# TMotor_Rev0_5_1_Mark_2_MAR17.net
KiCad netlist of a schematic drawn in EAGLE
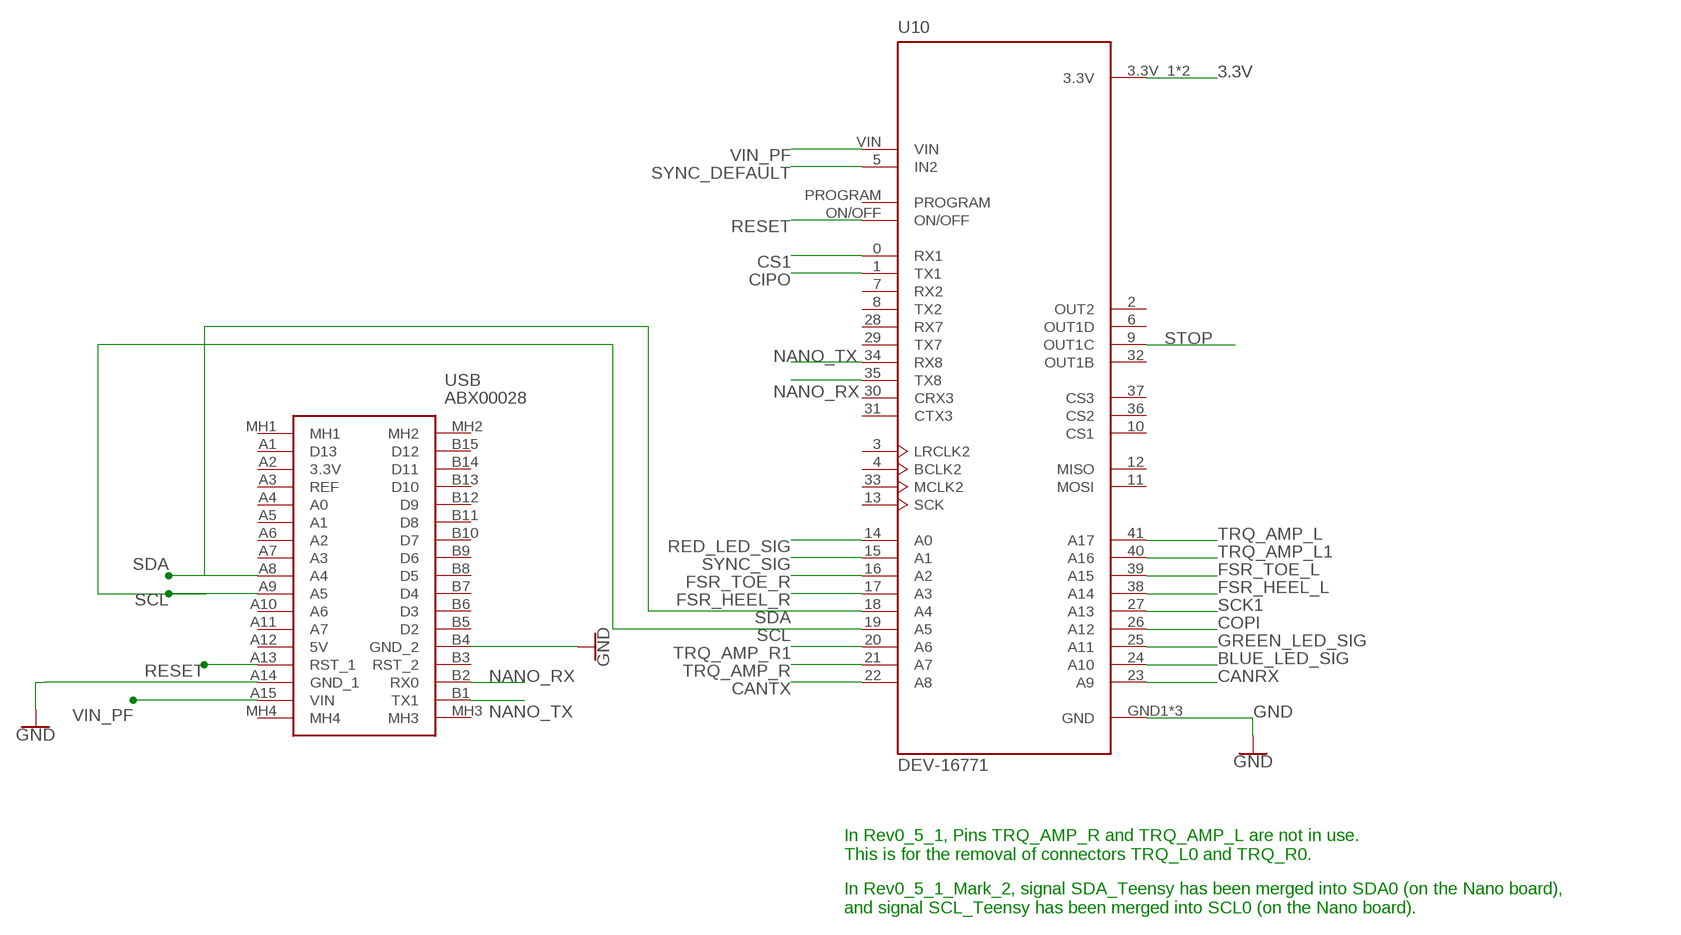
[diagram p0: schematic, sheet 1]
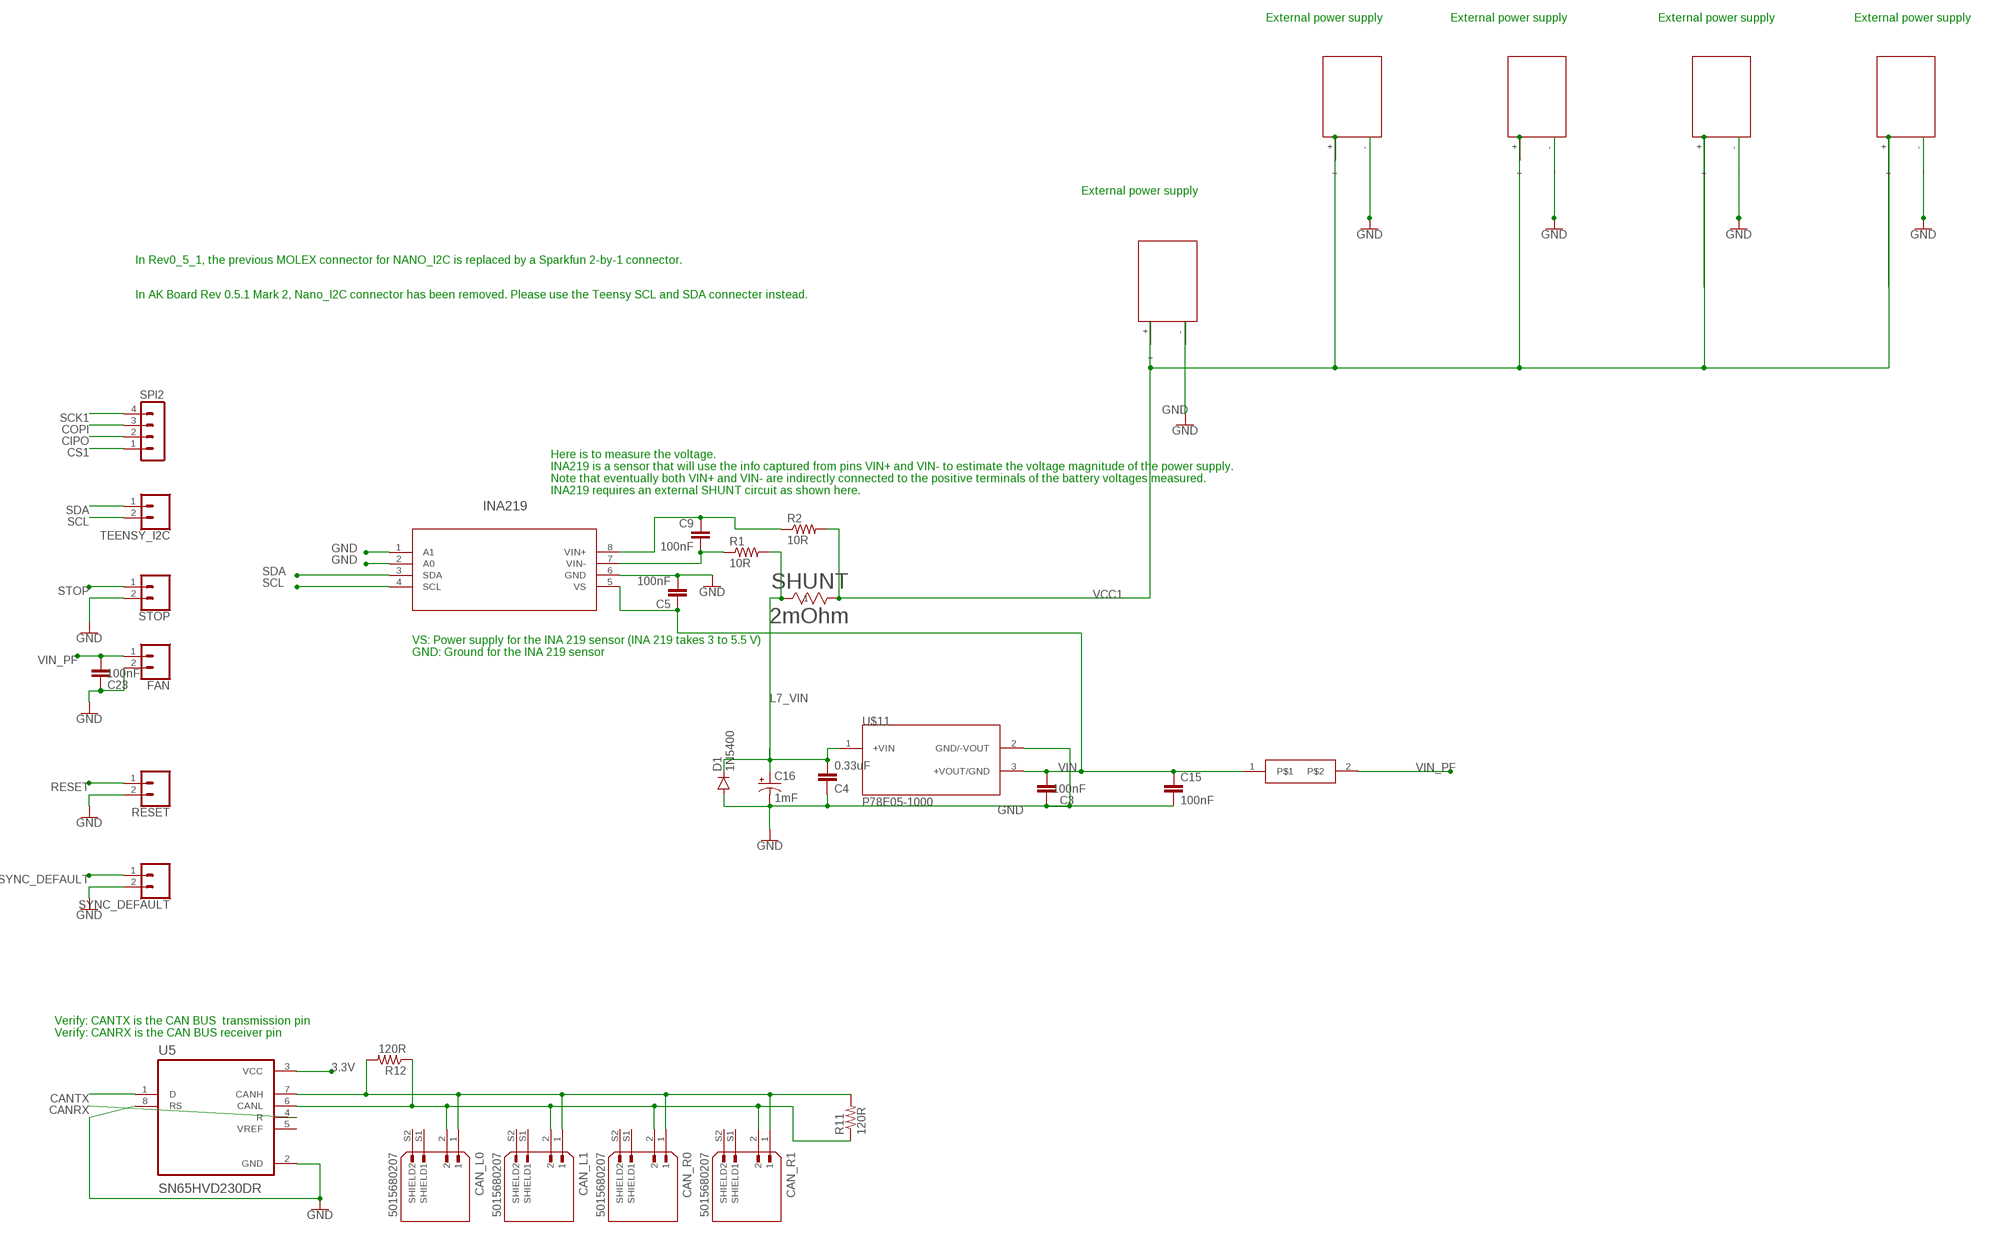
[diagram p1: schematic, sheet 2]
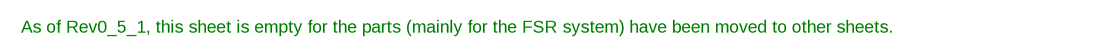
[diagram p2: schematic, sheet 3]
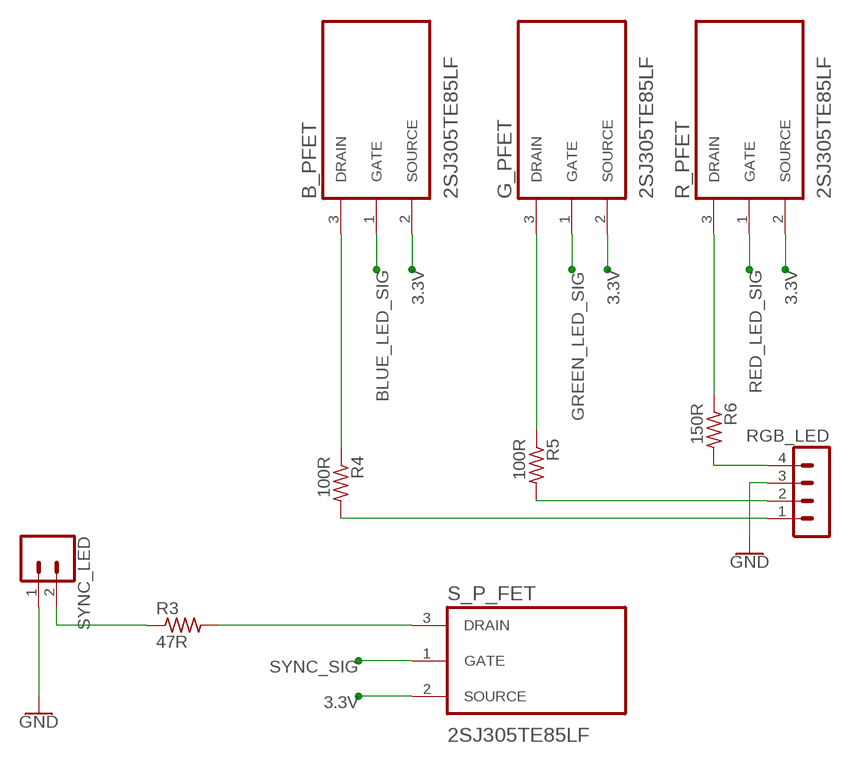
[diagram p3: schematic, sheet 4]
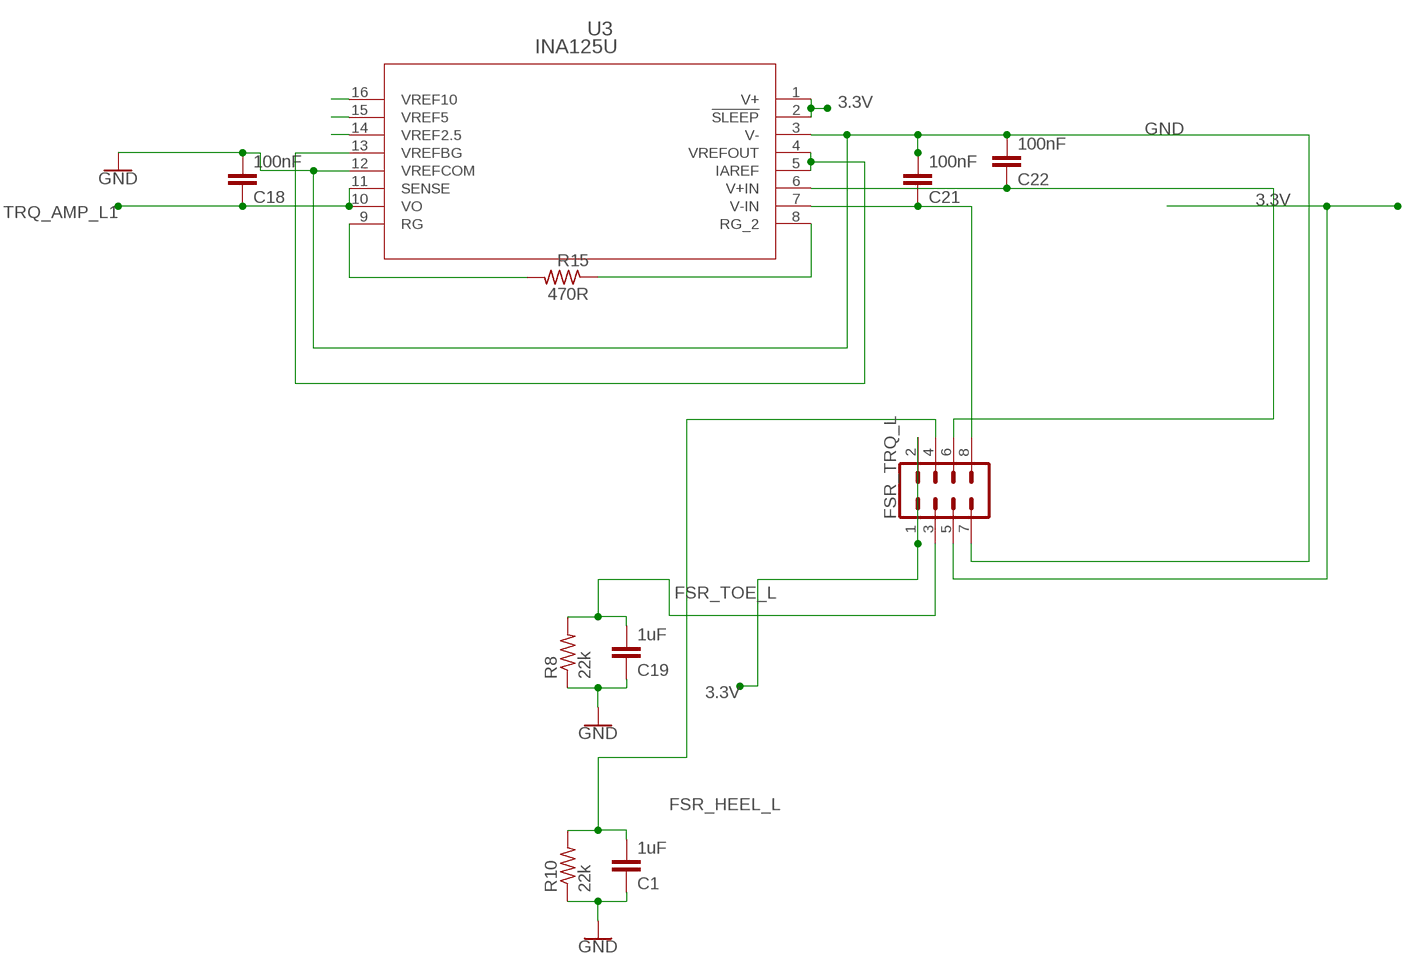
[diagram p4: schematic, sheet 5, part 1 of 2]
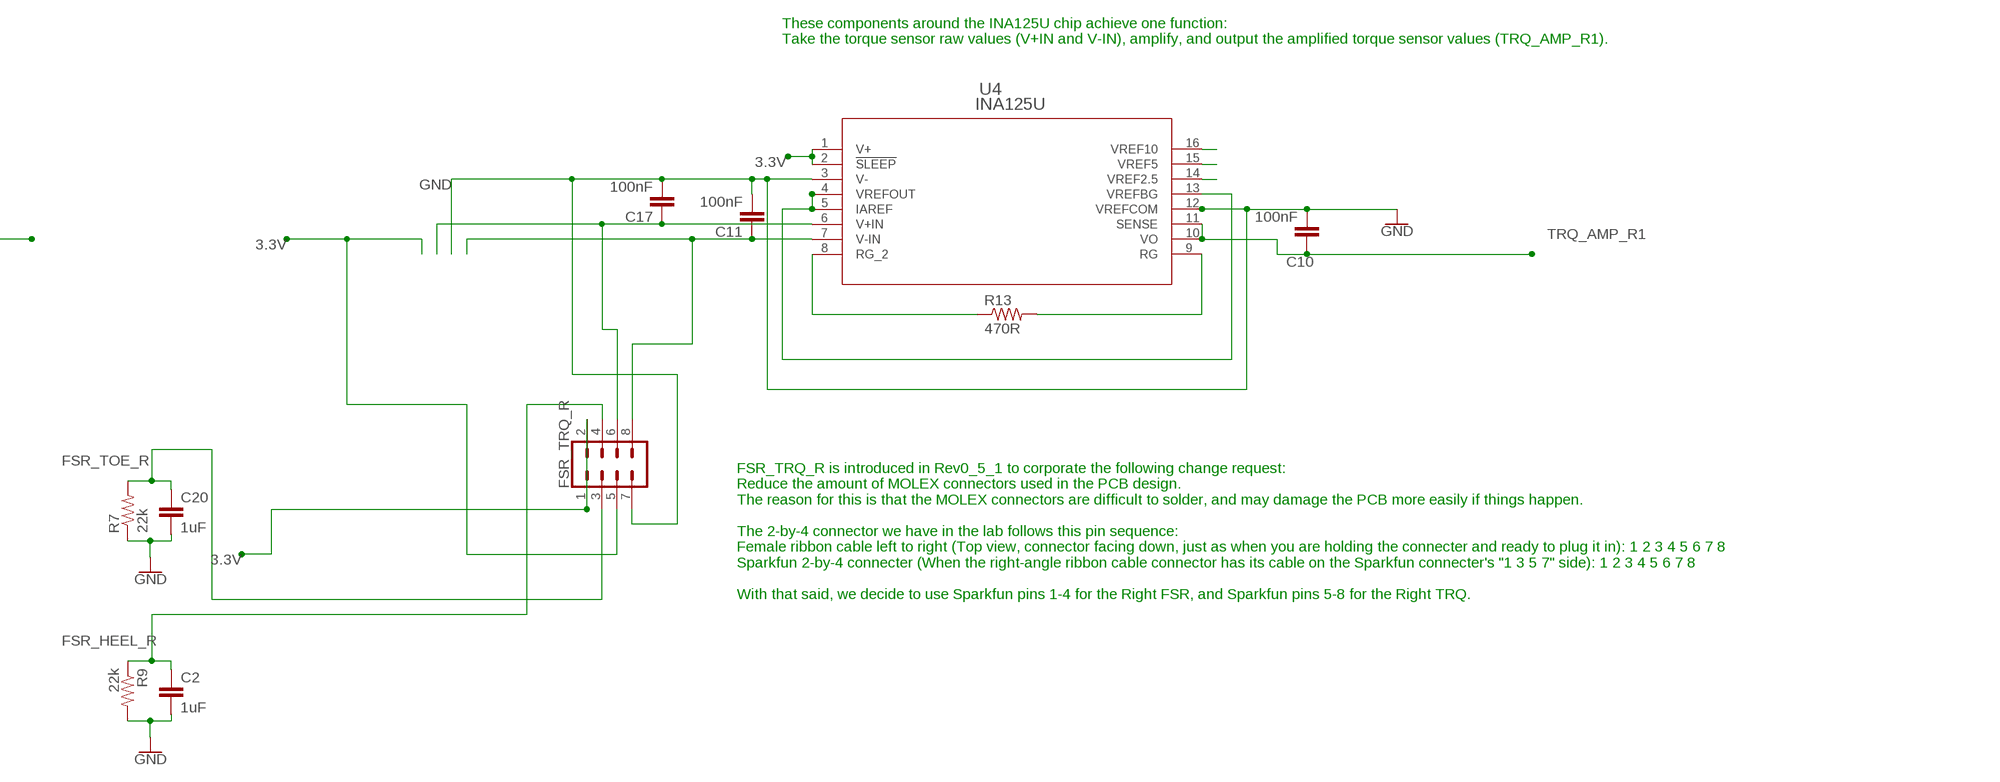
[diagram p5: schematic, sheet 5, part 2 of 2]

(export (version "E")
  (design (tool "Eeschema 10.0.6"))
  (components
    (comp (ref "B_PFET")
      (value "2SJ305TE85LF")
      (footprint "eagle-import:TRANS_SSM3J325F,LF")
      (fields (field (name "MF") "Toshiba"))
      (libsource (lib "eagle-import") (part "2SJ305TE85LF"))
    )
    (comp (ref "G_PFET")
      (value "2SJ305TE85LF")
      (footprint "eagle-import:TRANS_SSM3J325F,LF")
      (fields (field (name "MF") "Toshiba"))
      (libsource (lib "eagle-import") (part "2SJ305TE85LF"))
    )
    (comp (ref "R3")
      (value "47R")
      (footprint "eagle-import:0207_10")
      (libsource (lib "eagle-import") (part "R-US_0207/10"))
    )
    (comp (ref "R4")
      (value "100R")
      (footprint "eagle-import:0207_10")
      (libsource (lib "eagle-import") (part "R-US_0207/10"))
    )
    (comp (ref "R5")
      (value "100R")
      (footprint "eagle-import:0207_10")
      (libsource (lib "eagle-import") (part "R-US_0207/10"))
    )
    (comp (ref "R6")
      (value "150R")
      (footprint "eagle-import:0207_10")
      (libsource (lib "eagle-import") (part "R-US_0207/10"))
    )
    (comp (ref "RGB_LED")
      (value "MA04-1")
      (footprint "eagle-import:MA04-1")
      (libsource (lib "eagle-import") (part "MA04-1"))
    )
    (comp (ref "R_PFET")
      (value "2SJ305TE85LF")
      (footprint "eagle-import:TRANS_SSM3J325F,LF")
      (fields (field (name "MF") "Toshiba"))
      (libsource (lib "eagle-import") (part "2SJ305TE85LF"))
    )
    (comp (ref "SYNC_LED")
      (value "CONN_02")
      (footprint "eagle-import:1X02")
      (libsource (lib "eagle-import") (part "CONN_02"))
    )
    (comp (ref "S_P_FET")
      (value "2SJ305TE85LF")
      (footprint "eagle-import:TRANS_SSM3J325F,LF")
      (fields (field (name "MF") "Toshiba"))
      (libsource (lib "eagle-import") (part "2SJ305TE85LF"))
    )
    (comp (ref "U10")
      (value "DEV-16771")
      (footprint "eagle-import:MODULE_DEV-16771")
      (fields (field (name "MANUFACTURER") "SparkFun Electronics"))
      (libsource (lib "eagle-import") (part "DEV-16771"))
    )
    (comp (ref "USB")
      (value "ABX00028")
      (footprint "eagle-import:ABX00028")
      (fields (field (name "MOUSER_PART_NUMBER") "782-ABX00028"))
      (libsource (lib "eagle-import") (part "ABX00028"))
    )
    (comp (ref "C3")
      (value "100nF")
      (footprint "eagle-import:C050-024X044")
      (libsource (lib "eagle-import") (part "C-EU050-024X044"))
    )
    (comp (ref "C4")
      (value "0.33uF")
      (footprint "eagle-import:C050-024X044")
      (libsource (lib "eagle-import") (part "C-EU050-024X044"))
    )
    (comp (ref "C5")
      (value "100nF")
      (footprint "eagle-import:C050-024X044")
      (libsource (lib "eagle-import") (part "C-EU050-024X044"))
    )
    (comp (ref "C9")
      (value "100nF")
      (footprint "eagle-import:C050-024X044")
      (libsource (lib "eagle-import") (part "C-EU050-024X044"))
    )
    (comp (ref "C15")
      (value "100nF")
      (footprint "eagle-import:C050-024X044")
      (libsource (lib "eagle-import") (part "C-EU050-024X044"))
    )
    (comp (ref "C16")
      (value "1mF")
      (footprint "eagle-import:E5-10,5")
      (libsource (lib "eagle-import") (part "CPOL-USE5-10.5"))
    )
    (comp (ref "C23")
      (value "100nF")
      (footprint "eagle-import:C050-024X044")
      (libsource (lib "eagle-import") (part "C-EU050-024X044"))
    )
    (comp (ref "CAN_L0")
      (value "5015680207")
      (footprint "eagle-import:MOLEX_5015680207")
      (fields (field (name "MANUFACTURER") "Molex"))
      (libsource (lib "eagle-import") (part "5015680207"))
    )
    (comp (ref "CAN_L1")
      (value "5015680207")
      (footprint "eagle-import:MOLEX_5015680207")
      (fields (field (name "MANUFACTURER") "Molex"))
      (libsource (lib "eagle-import") (part "5015680207"))
    )
    (comp (ref "CAN_R0")
      (value "5015680207")
      (footprint "eagle-import:MOLEX_5015680207")
      (fields (field (name "MANUFACTURER") "Molex"))
      (libsource (lib "eagle-import") (part "5015680207"))
    )
    (comp (ref "CAN_R1")
      (value "5015680207")
      (footprint "eagle-import:MOLEX_5015680207")
      (fields (field (name "MANUFACTURER") "Molex"))
      (libsource (lib "eagle-import") (part "5015680207"))
    )
    (comp (ref "D1")
      (value "1N5400")
      (footprint "eagle-import:DO201-15")
      (libsource (lib "eagle-import") (part "1N5400"))
    )
    (comp (ref "FAN")
      (value "CONN_02")
      (footprint "eagle-import:1X02")
      (libsource (lib "eagle-import") (part "CONN_02"))
    )
    (comp (ref "INA219")
      (value "INA219AIDR")
      (footprint "eagle-import:D8_TEX")
      (libsource (lib "eagle-import") (part "INA219AIDR"))
    )
    (comp (ref "R1")
      (value "10R")
      (footprint "eagle-import:0207_10")
      (libsource (lib "eagle-import") (part "R-US_0207/10"))
    )
    (comp (ref "R2")
      (value "10R")
      (footprint "eagle-import:0207_10")
      (libsource (lib "eagle-import") (part "R-US_0207/10"))
    )
    (comp (ref "R11")
      (value "120R")
      (footprint "eagle-import:0207_10")
      (libsource (lib "eagle-import") (part "R-US_0207/10"))
    )
    (comp (ref "R12")
      (value "120R")
      (footprint "eagle-import:0207_10")
      (libsource (lib "eagle-import") (part "R-US_0207/10"))
    )
    (comp (ref "RESET")
      (value "CONN_02")
      (footprint "eagle-import:1X02")
      (libsource (lib "eagle-import") (part "CONN_02"))
    )
    (comp (ref "SHUNT")
      (value "2mOhm")
      (footprint "eagle-import:STA_CSNL2512(2)_STP")
      (fields (field (name "MANUFACTURER_PART_NUMBER") "CSNL2512FT2L00"))
      (libsource (lib "eagle-import") (part "CSNL2512FT2L00"))
    )
    (comp (ref "SPI2")
      (value "MA04-1")
      (footprint "eagle-import:MA04-1")
      (libsource (lib "eagle-import") (part "MA04-1"))
    )
    (comp (ref "STOP")
      (value "CONN_02")
      (footprint "eagle-import:1X02")
      (libsource (lib "eagle-import") (part "CONN_02"))
    )
    (comp (ref "SYNC_DEFAULT")
      (value "CONN_02")
      (footprint "eagle-import:1X02")
      (libsource (lib "eagle-import") (part "CONN_02"))
    )
    (comp (ref "TEENSY_I2C")
      (value "CONN_02")
      (footprint "eagle-import:1X02")
      (libsource (lib "eagle-import") (part "CONN_02"))
    )
    (comp (ref "U$6")
      (value "0458002.DR")
      (footprint "eagle-import:FUSE_LITTEL_448")
      (libsource (lib "eagle-import") (part "0458002.DR"))
    )
    (comp (ref "U$11")
      (value "P78E05-1000")
      (footprint "eagle-import:P78E05-1000")
      (libsource (lib "eagle-import") (part "P78E05-1000"))
    )
    (comp (ref "U5")
      (value "SN65HVD230DR")
      (footprint "eagle-import:SOIC127P599X175-8N")
      (fields (field (name "MF") "Texas Instruments"))
      (libsource (lib "eagle-import") (part "SN65HVD230DR"))
    )
    (comp (ref "XT30UPB-F")
      (value "L_0")
      (footprint "eagle-import:XT30UPB-F")
      (libsource (lib "eagle-import") (part "XT30UPB-F"))
    )
    (comp (ref "XT30UPB-F1")
      (value "L_0")
      (footprint "eagle-import:XT30UPB-F")
      (libsource (lib "eagle-import") (part "XT30UPB-F"))
    )
    (comp (ref "XT30UPB-F2")
      (value "L_0")
      (footprint "eagle-import:XT30UPB-F")
      (libsource (lib "eagle-import") (part "XT30UPB-F"))
    )
    (comp (ref "XT30UPB-F3")
      (value "L_0")
      (footprint "eagle-import:XT30UPB-F")
      (libsource (lib "eagle-import") (part "XT30UPB-F"))
    )
    (comp (ref "XT30UPB-F4")
      (value "L_0")
      (footprint "eagle-import:XT30UPB-F")
      (libsource (lib "eagle-import") (part "XT30UPB-F"))
    )
    (comp (ref "C1")
      (value "1uF")
      (footprint "eagle-import:C050-024X044")
      (libsource (lib "eagle-import") (part "C-EU050-024X044"))
    )
    (comp (ref "C2")
      (value "1uF")
      (footprint "eagle-import:C050-024X044")
      (libsource (lib "eagle-import") (part "C-EU050-024X044"))
    )
    (comp (ref "C10")
      (value "100nF")
      (footprint "eagle-import:C050-024X044")
      (libsource (lib "eagle-import") (part "C-EU050-024X044"))
    )
    (comp (ref "C11")
      (value "100nF")
      (footprint "eagle-import:C050-024X044")
      (libsource (lib "eagle-import") (part "C-EU050-024X044"))
    )
    (comp (ref "C17")
      (value "100nF")
      (footprint "eagle-import:C050-024X044")
      (libsource (lib "eagle-import") (part "C-EU050-024X044"))
    )
    (comp (ref "C18")
      (value "100nF")
      (footprint "eagle-import:C050-024X044")
      (libsource (lib "eagle-import") (part "C-EU050-024X044"))
    )
    (comp (ref "C19")
      (value "1uF")
      (footprint "eagle-import:C050-024X044")
      (libsource (lib "eagle-import") (part "C-EU050-024X044"))
    )
    (comp (ref "C20")
      (value "1uF")
      (footprint "eagle-import:C050-024X044")
      (libsource (lib "eagle-import") (part "C-EU050-024X044"))
    )
    (comp (ref "C21")
      (value "100nF")
      (footprint "eagle-import:C050-024X044")
      (libsource (lib "eagle-import") (part "C-EU050-024X044"))
    )
    (comp (ref "C22")
      (value "100nF")
      (footprint "eagle-import:C050-024X044")
      (libsource (lib "eagle-import") (part "C-EU050-024X044"))
    )
    (comp (ref "FSR_TRQ_L")
      (value "CONN_04X2")
      (footprint "eagle-import:2X4")
      (libsource (lib "eagle-import") (part "CONN_04X2"))
    )
    (comp (ref "FSR_TRQ_R")
      (value "CONN_04X2")
      (footprint "eagle-import:2X4")
      (libsource (lib "eagle-import") (part "CONN_04X2"))
    )
    (comp (ref "R7")
      (value "22k")
      (footprint "eagle-import:0207_10")
      (libsource (lib "eagle-import") (part "resistor_348_R-US_0207/10"))
    )
    (comp (ref "R8")
      (value "22k")
      (footprint "eagle-import:0207_10")
      (libsource (lib "eagle-import") (part "resistor_348_R-US_0207/10"))
    )
    (comp (ref "R9")
      (value "22k")
      (footprint "eagle-import:0207_10")
      (libsource (lib "eagle-import") (part "resistor_348_R-US_0207/10"))
    )
    (comp (ref "R10")
      (value "22k")
      (footprint "eagle-import:0207_10")
      (libsource (lib "eagle-import") (part "resistor_348_R-US_0207/10"))
    )
    (comp (ref "R13")
      (value "470R")
      (footprint "eagle-import:0207_10")
      (libsource (lib "eagle-import") (part "R-US_0207/10"))
    )
    (comp (ref "R15")
      (value "470R")
      (footprint "eagle-import:0207_10")
      (libsource (lib "eagle-import") (part "R-US_0207/10"))
    )
    (comp (ref "U3")
      (value "INA125U")
      (footprint "eagle-import:D16")
      (fields (field (name "GENERIC_PART_NUMBER") "INA125") (field (name "MANUFACTURER") "Texas Instruments"))
      (libsource (lib "eagle-import") (part "INA125U"))
    )
    (comp (ref "U4")
      (value "INA125U")
      (footprint "eagle-import:D16")
      (fields (field (name "GENERIC_PART_NUMBER") "INA125") (field (name "MANUFACTURER") "Texas Instruments"))
      (libsource (lib "eagle-import") (part "INA125U"))
    )
  )
  (nets
    (net (code "1") (name "3.3V") (class "Default")
      (node (ref "B_PFET") (pin "2") (pinfunction "SOURCE_2") (pintype "bidirectional"))
      (node (ref "FSR_TRQ_L") (pin "1") (pinfunction "1_1") (pintype "passive"))
      (node (ref "FSR_TRQ_L") (pin "2") (pinfunction "2_2") (pintype "passive"))
      (node (ref "FSR_TRQ_L") (pin "5") (pinfunction "5_5") (pintype "passive"))
      (node (ref "FSR_TRQ_R") (pin "1") (pinfunction "1_1") (pintype "passive"))
      (node (ref "FSR_TRQ_R") (pin "2") (pinfunction "2_2") (pintype "passive"))
      (node (ref "FSR_TRQ_R") (pin "5") (pinfunction "5_5") (pintype "passive"))
      (node (ref "G_PFET") (pin "2") (pinfunction "SOURCE_2") (pintype "bidirectional"))
      (node (ref "R_PFET") (pin "2") (pinfunction "SOURCE_2") (pintype "bidirectional"))
      (node (ref "S_P_FET") (pin "2") (pinfunction "SOURCE_2") (pintype "bidirectional"))
      (node (ref "U10") (pin "3.3V_1") (pinfunction "3.3V_3.3V_1") (pintype "power_in"))
      (node (ref "U10") (pin "3.3V_2") (pinfunction "3.3V_3.3V_2") (pintype "power_in"))
      (node (ref "U3") (pin "1") (pinfunction "V+_1") (pintype "power_in"))
      (node (ref "U3") (pin "2") (pinfunction "~{SLEEP}_2") (pintype "passive"))
      (node (ref "U4") (pin "1") (pinfunction "V+_1") (pintype "power_in"))
      (node (ref "U4") (pin "2") (pinfunction "~{SLEEP}_2") (pintype "passive"))
      (node (ref "U5") (pin "3") (pinfunction "VCC_3") (pintype "power_in"))
    )
    (net (code "2") (name "BLUE_LED_SIG") (class "Default")
      (node (ref "B_PFET") (pin "1") (pinfunction "GATE_1") (pintype "bidirectional"))
      (node (ref "U10") (pin "24") (pinfunction "A10_24") (pintype "bidirectional"))
    )
    (net (code "3") (name "CANRX") (class "Default")
      (node (ref "U10") (pin "23") (pinfunction "A9_23") (pintype "bidirectional"))
      (node (ref "U5") (pin "4") (pinfunction "R_4") (pintype "output"))
    )
    (net (code "4") (name "CANTX") (class "Default")
      (node (ref "U10") (pin "22") (pinfunction "A8_22") (pintype "bidirectional"))
      (node (ref "U5") (pin "1") (pinfunction "D_1") (pintype "input"))
    )
    (net (code "5") (name "CIPO") (class "Default")
      (node (ref "SPI2") (pin "2") (pinfunction "2_2") (pintype "passive"))
      (node (ref "U10") (pin "1") (pinfunction "TX1_1") (pintype "bidirectional"))
    )
    (net (code "6") (name "COPI") (class "Default")
      (node (ref "SPI2") (pin "3") (pinfunction "3_3") (pintype "passive"))
      (node (ref "U10") (pin "26") (pinfunction "A12_26") (pintype "bidirectional"))
    )
    (net (code "7") (name "CS1") (class "Default")
      (node (ref "SPI2") (pin "1") (pinfunction "1_1") (pintype "passive"))
      (node (ref "U10") (pin "0") (pinfunction "RX1_0") (pintype "bidirectional"))
    )
    (net (code "8") (name "FSR_HEEL_L") (class "Default")
      (node (ref "C1") (pin "2") (pinfunction "2_2") (pintype "passive"))
      (node (ref "FSR_TRQ_L") (pin "4") (pinfunction "4_4") (pintype "passive"))
      (node (ref "R10") (pin "2") (pinfunction "2_2") (pintype "passive"))
      (node (ref "U10") (pin "38") (pinfunction "A14_38") (pintype "bidirectional"))
    )
    (net (code "9") (name "FSR_HEEL_R") (class "Default")
      (node (ref "C2") (pin "1") (pinfunction "1_1") (pintype "passive"))
      (node (ref "FSR_TRQ_R") (pin "4") (pinfunction "4_4") (pintype "passive"))
      (node (ref "R9") (pin "1") (pinfunction "1_1") (pintype "passive"))
      (node (ref "U10") (pin "17") (pinfunction "A3_17") (pintype "bidirectional"))
    )
    (net (code "10") (name "FSR_TOE_L") (class "Default")
      (node (ref "C19") (pin "2") (pinfunction "2_2") (pintype "passive"))
      (node (ref "FSR_TRQ_L") (pin "3") (pinfunction "3_3") (pintype "passive"))
      (node (ref "R8") (pin "2") (pinfunction "2_2") (pintype "passive"))
      (node (ref "U10") (pin "39") (pinfunction "A15_39") (pintype "bidirectional"))
    )
    (net (code "11") (name "FSR_TOE_R") (class "Default")
      (node (ref "C20") (pin "1") (pinfunction "1_1") (pintype "passive"))
      (node (ref "FSR_TRQ_R") (pin "3") (pinfunction "3_3") (pintype "passive"))
      (node (ref "R7") (pin "2") (pinfunction "2_2") (pintype "passive"))
      (node (ref "U10") (pin "16") (pinfunction "A2_16") (pintype "bidirectional"))
    )
    (net (code "12") (name "GND") (class "Default")
      (node (ref "C1") (pin "1") (pinfunction "1_1") (pintype "passive"))
      (node (ref "C10") (pin "2") (pinfunction "2_2") (pintype "passive"))
      (node (ref "C11") (pin "2") (pinfunction "2_2") (pintype "passive"))
      (node (ref "C15") (pin "2") (pinfunction "2_2") (pintype "passive"))
      (node (ref "C16") (pin "-") (pinfunction "-_-") (pintype "passive"))
      (node (ref "C17") (pin "2") (pinfunction "2_2") (pintype "passive"))
      (node (ref "C18") (pin "2") (pinfunction "2_2") (pintype "passive"))
      (node (ref "C19") (pin "1") (pinfunction "1_1") (pintype "passive"))
      (node (ref "C2") (pin "2") (pinfunction "2_2") (pintype "passive"))
      (node (ref "C20") (pin "2") (pinfunction "2_2") (pintype "passive"))
      (node (ref "C21") (pin "2") (pinfunction "2_2") (pintype "passive"))
      (node (ref "C22") (pin "2") (pinfunction "2_2") (pintype "passive"))
      (node (ref "C23") (pin "1") (pinfunction "1_1") (pintype "passive"))
      (node (ref "C3") (pin "1") (pinfunction "1_1") (pintype "passive"))
      (node (ref "C4") (pin "1") (pinfunction "1_1") (pintype "passive"))
      (node (ref "C5") (pin "2") (pinfunction "2_2") (pintype "passive"))
      (node (ref "D1") (pin "A") (pinfunction "A_A") (pintype "passive"))
      (node (ref "FAN") (pin "2") (pinfunction "2_2") (pintype "passive"))
      (node (ref "FSR_TRQ_L") (pin "7") (pinfunction "7_7") (pintype "passive"))
      (node (ref "FSR_TRQ_R") (pin "7") (pinfunction "7_7") (pintype "passive"))
      (node (ref "INA219") (pin "1") (pinfunction "A1_1") (pintype "passive"))
      (node (ref "INA219") (pin "2") (pinfunction "A0_2") (pintype "passive"))
      (node (ref "INA219") (pin "6") (pinfunction "GND_6") (pintype "power_in"))
      (node (ref "R10") (pin "1") (pinfunction "1_1") (pintype "passive"))
      (node (ref "R7") (pin "1") (pinfunction "1_1") (pintype "passive"))
      (node (ref "R8") (pin "1") (pinfunction "1_1") (pintype "passive"))
      (node (ref "R9") (pin "2") (pinfunction "2_2") (pintype "passive"))
      (node (ref "RESET") (pin "2") (pinfunction "2_2") (pintype "passive"))
      (node (ref "RGB_LED") (pin "3") (pinfunction "3_3") (pintype "passive"))
      (node (ref "STOP") (pin "2") (pinfunction "2_2") (pintype "passive"))
      (node (ref "SYNC_DEFAULT") (pin "2") (pinfunction "2_2") (pintype "passive"))
      (node (ref "SYNC_LED") (pin "1") (pinfunction "1_1") (pintype "passive"))
      (node (ref "U$11") (pin "2") (pinfunction "GND/-VOUT_2") (pintype "power_in"))
      (node (ref "U10") (pin "GND1") (pinfunction "GND_GND1") (pintype "power_in"))
      (node (ref "U10") (pin "GND2") (pinfunction "GND_GND2") (pintype "power_in"))
      (node (ref "U10") (pin "GND3") (pinfunction "GND_GND3") (pintype "power_in"))
      (node (ref "U3") (pin "12") (pinfunction "VREFCOM_12") (pintype "power_in"))
      (node (ref "U3") (pin "3") (pinfunction "V-_3") (pintype "power_in"))
      (node (ref "U4") (pin "12") (pinfunction "VREFCOM_12") (pintype "power_in"))
      (node (ref "U4") (pin "3") (pinfunction "V-_3") (pintype "power_in"))
      (node (ref "U5") (pin "2") (pinfunction "GND_2") (pintype "power_in"))
      (node (ref "U5") (pin "8") (pinfunction "RS_8") (pintype "input"))
      (node (ref "USB") (pin "A14") (pinfunction "GND_1_A14") (pintype "bidirectional"))
      (node (ref "USB") (pin "B4") (pinfunction "GND_2_B4") (pintype "bidirectional"))
      (node (ref "XT30UPB-F") (pin "-") (pinfunction "-_-") (pintype "output"))
      (node (ref "XT30UPB-F1") (pin "-") (pinfunction "-_-") (pintype "output"))
      (node (ref "XT30UPB-F2") (pin "-") (pinfunction "-_-") (pintype "output"))
      (node (ref "XT30UPB-F3") (pin "-") (pinfunction "-_-") (pintype "output"))
      (node (ref "XT30UPB-F4") (pin "-") (pinfunction "-_-") (pintype "output"))
    )
    (net (code "13") (name "GREEN_LED_SIG") (class "Default")
      (node (ref "G_PFET") (pin "1") (pinfunction "GATE_1") (pintype "bidirectional"))
      (node (ref "U10") (pin "25") (pinfunction "A11_25") (pintype "bidirectional"))
    )
    (net (code "14") (name "L7_VIN") (class "Default")
      (node (ref "C16") (pin "+") (pinfunction "+_+") (pintype "passive"))
      (node (ref "C4") (pin "2") (pinfunction "2_2") (pintype "passive"))
      (node (ref "D1") (pin "C") (pinfunction "C_C") (pintype "passive"))
      (node (ref "R1") (pin "2") (pinfunction "2_2") (pintype "passive"))
      (node (ref "SHUNT") (pin "1") (pinfunction "1_1") (pintype "passive"))
      (node (ref "U$11") (pin "1") (pinfunction "+VIN_1") (pintype "input"))
    )
    (net (code "15") (name "NANO_RX") (class "Default")
      (node (ref "U10") (pin "35") (pinfunction "TX8_35") (pintype "bidirectional"))
      (node (ref "USB") (pin "B2") (pinfunction "RX0_B2") (pintype "bidirectional"))
    )
    (net (code "16") (name "NANO_TX") (class "Default")
      (node (ref "U10") (pin "34") (pinfunction "RX8_34") (pintype "bidirectional"))
      (node (ref "USB") (pin "B1") (pinfunction "TX1_B1") (pintype "bidirectional"))
    )
    (net (code "17") (name "Net-(B_PFET-DRAIN)") (class "Default")
      (node (ref "B_PFET") (pin "3") (pinfunction "DRAIN_3") (pintype "input"))
      (node (ref "R4") (pin "1") (pinfunction "1_1") (pintype "passive"))
    )
    (net (code "18") (name "Net-(G_PFET-DRAIN)") (class "Default")
      (node (ref "G_PFET") (pin "3") (pinfunction "DRAIN_3") (pintype "input"))
      (node (ref "R5") (pin "1") (pinfunction "1_1") (pintype "passive"))
    )
    (net (code "19") (name "Net-(INA219-VIN+)") (class "Default")
      (node (ref "C9") (pin "1") (pinfunction "1_1") (pintype "passive"))
      (node (ref "INA219") (pin "8") (pinfunction "VIN+_8") (pintype "input"))
      (node (ref "R2") (pin "1") (pinfunction "1_1") (pintype "passive"))
    )
    (net (code "20") (name "Net-(INA219-VIN-)") (class "Default")
      (node (ref "C9") (pin "2") (pinfunction "2_2") (pintype "passive"))
      (node (ref "INA219") (pin "7") (pinfunction "VIN-_7") (pintype "input"))
      (node (ref "R1") (pin "1") (pinfunction "1_1") (pintype "passive"))
    )
    (net (code "21") (name "Net-(R3-Pad1)") (class "Default")
      (node (ref "R3") (pin "1") (pinfunction "1_1") (pintype "passive"))
      (node (ref "SYNC_LED") (pin "2") (pinfunction "2_2") (pintype "passive"))
    )
    (net (code "22") (name "Net-(R4-Pad2)") (class "Default")
      (node (ref "R4") (pin "2") (pinfunction "2_2") (pintype "passive"))
      (node (ref "RGB_LED") (pin "1") (pinfunction "1_1") (pintype "passive"))
    )
    (net (code "23") (name "Net-(R5-Pad2)") (class "Default")
      (node (ref "R5") (pin "2") (pinfunction "2_2") (pintype "passive"))
      (node (ref "RGB_LED") (pin "2") (pinfunction "2_2") (pintype "passive"))
    )
    (net (code "24") (name "Net-(R6-Pad2)") (class "Default")
      (node (ref "R6") (pin "2") (pinfunction "2_2") (pintype "passive"))
      (node (ref "RGB_LED") (pin "4") (pinfunction "4_4") (pintype "passive"))
    )
    (net (code "25") (name "Net-(R_PFET-DRAIN)") (class "Default")
      (node (ref "R6") (pin "1") (pinfunction "1_1") (pintype "passive"))
      (node (ref "R_PFET") (pin "3") (pinfunction "DRAIN_3") (pintype "input"))
    )
    (net (code "26") (name "Net-(S_P_FET-DRAIN)") (class "Default")
      (node (ref "R3") (pin "2") (pinfunction "2_2") (pintype "passive"))
      (node (ref "S_P_FET") (pin "3") (pinfunction "DRAIN_3") (pintype "input"))
    )
    (net (code "27") (name "Net-(U3-IAREF)") (class "Default")
      (node (ref "U3") (pin "13") (pinfunction "VREFBG_13") (pintype "power_in"))
      (node (ref "U3") (pin "4") (pinfunction "VREFOUT_4") (pintype "output"))
      (node (ref "U3") (pin "5") (pinfunction "IAREF_5") (pintype "passive"))
    )
    (net (code "28") (name "Net-(U3-RG)") (class "Default")
      (node (ref "R15") (pin "2") (pinfunction "2_2") (pintype "passive"))
      (node (ref "U3") (pin "9") (pinfunction "RG_9") (pintype "passive"))
    )
    (net (code "29") (name "Net-(U3-RG_2)") (class "Default")
      (node (ref "R15") (pin "1") (pinfunction "1_1") (pintype "passive"))
      (node (ref "U3") (pin "8") (pinfunction "RG_2_8") (pintype "passive"))
    )
    (net (code "30") (name "Net-(U3-V+IN)") (class "Default")
      (node (ref "C22") (pin "1") (pinfunction "1_1") (pintype "passive"))
      (node (ref "FSR_TRQ_L") (pin "6") (pinfunction "6_6") (pintype "passive"))
      (node (ref "U3") (pin "6") (pinfunction "V+IN_6") (pintype "input"))
    )
    (net (code "31") (name "Net-(U3-V-IN)") (class "Default")
      (node (ref "C21") (pin "1") (pinfunction "1_1") (pintype "passive"))
      (node (ref "FSR_TRQ_L") (pin "8") (pinfunction "8_8") (pintype "passive"))
      (node (ref "U3") (pin "7") (pinfunction "V-IN_7") (pintype "input"))
    )
    (net (code "32") (name "Net-(U4-IAREF)") (class "Default")
      (node (ref "U4") (pin "13") (pinfunction "VREFBG_13") (pintype "power_in"))
      (node (ref "U4") (pin "4") (pinfunction "VREFOUT_4") (pintype "output"))
      (node (ref "U4") (pin "5") (pinfunction "IAREF_5") (pintype "passive"))
    )
    (net (code "33") (name "Net-(U4-RG)") (class "Default")
      (node (ref "R13") (pin "2") (pinfunction "2_2") (pintype "passive"))
      (node (ref "U4") (pin "9") (pinfunction "RG_9") (pintype "passive"))
    )
    (net (code "34") (name "Net-(U4-RG_2)") (class "Default")
      (node (ref "R13") (pin "1") (pinfunction "1_1") (pintype "passive"))
      (node (ref "U4") (pin "8") (pinfunction "RG_2_8") (pintype "passive"))
    )
    (net (code "35") (name "Net-(U4-V+IN)") (class "Default")
      (node (ref "C17") (pin "1") (pinfunction "1_1") (pintype "passive"))
      (node (ref "FSR_TRQ_R") (pin "6") (pinfunction "6_6") (pintype "passive"))
      (node (ref "U4") (pin "6") (pinfunction "V+IN_6") (pintype "input"))
    )
    (net (code "36") (name "Net-(U4-V-IN)") (class "Default")
      (node (ref "C11") (pin "1") (pinfunction "1_1") (pintype "passive"))
      (node (ref "FSR_TRQ_R") (pin "8") (pinfunction "8_8") (pintype "passive"))
      (node (ref "U4") (pin "7") (pinfunction "V-IN_7") (pintype "input"))
    )
    (net (code "37") (name "Net-(U5-CANH)") (class "Default")
      (node (ref "CAN_L0") (pin "1") (pinfunction "1_1") (pintype "passive"))
      (node (ref "CAN_L1") (pin "1") (pinfunction "1_1") (pintype "passive"))
      (node (ref "CAN_R0") (pin "1") (pinfunction "1_1") (pintype "passive"))
      (node (ref "CAN_R1") (pin "1") (pinfunction "1_1") (pintype "passive"))
      (node (ref "R11") (pin "2") (pinfunction "2_2") (pintype "passive"))
      (node (ref "R12") (pin "2") (pinfunction "2_2") (pintype "passive"))
      (node (ref "U5") (pin "7") (pinfunction "CANH_7") (pintype "output"))
    )
    (net (code "38") (name "Net-(U5-CANL)") (class "Default")
      (node (ref "CAN_L0") (pin "2") (pinfunction "2_2") (pintype "passive"))
      (node (ref "CAN_L1") (pin "2") (pinfunction "2_2") (pintype "passive"))
      (node (ref "CAN_R0") (pin "2") (pinfunction "2_2") (pintype "passive"))
      (node (ref "CAN_R1") (pin "2") (pinfunction "2_2") (pintype "passive"))
      (node (ref "R11") (pin "1") (pinfunction "1_1") (pintype "passive"))
      (node (ref "R12") (pin "1") (pinfunction "1_1") (pintype "passive"))
      (node (ref "U5") (pin "6") (pinfunction "CANL_6") (pintype "output"))
    )
    (net (code "39") (name "RED_LED_SIG") (class "Default")
      (node (ref "R_PFET") (pin "1") (pinfunction "GATE_1") (pintype "bidirectional"))
      (node (ref "U10") (pin "14") (pinfunction "A0_14") (pintype "bidirectional"))
    )
    (net (code "40") (name "RESET") (class "Default")
      (node (ref "RESET") (pin "1") (pinfunction "1_1") (pintype "passive"))
      (node (ref "U10") (pin "ON/OFF") (pinfunction "ON/OFF_ON/OFF") (pintype "bidirectional"))
      (node (ref "USB") (pin "A13") (pinfunction "RST_1_A13") (pintype "bidirectional"))
    )
    (net (code "41") (name "SCK1") (class "Default")
      (node (ref "SPI2") (pin "4") (pinfunction "4_4") (pintype "passive"))
      (node (ref "U10") (pin "27") (pinfunction "A13_27") (pintype "bidirectional"))
    )
    (net (code "42") (name "SCL") (class "Default")
      (node (ref "INA219") (pin "4") (pinfunction "SCL_4") (pintype "passive"))
      (node (ref "TEENSY_I2C") (pin "2") (pinfunction "2_2") (pintype "passive"))
      (node (ref "U10") (pin "19") (pinfunction "A5_19") (pintype "bidirectional"))
      (node (ref "USB") (pin "A9") (pinfunction "A5_A9") (pintype "bidirectional"))
    )
    (net (code "43") (name "SDA") (class "Default")
      (node (ref "INA219") (pin "3") (pinfunction "SDA_3") (pintype "passive"))
      (node (ref "TEENSY_I2C") (pin "1") (pinfunction "1_1") (pintype "passive"))
      (node (ref "U10") (pin "18") (pinfunction "A4_18") (pintype "bidirectional"))
      (node (ref "USB") (pin "A8") (pinfunction "A4_A8") (pintype "bidirectional"))
    )
    (net (code "44") (name "STOP") (class "Default")
      (node (ref "STOP") (pin "1") (pinfunction "1_1") (pintype "passive"))
      (node (ref "U10") (pin "9") (pinfunction "OUT1C_9") (pintype "output"))
    )
    (net (code "45") (name "SYNC_DEFAULT") (class "Default")
      (node (ref "SYNC_DEFAULT") (pin "1") (pinfunction "1_1") (pintype "passive"))
      (node (ref "U10") (pin "5") (pinfunction "IN2_5") (pintype "bidirectional"))
    )
    (net (code "46") (name "SYNC_SIG") (class "Default")
      (node (ref "S_P_FET") (pin "1") (pinfunction "GATE_1") (pintype "bidirectional"))
      (node (ref "U10") (pin "15") (pinfunction "A1_15") (pintype "bidirectional"))
    )
    (net (code "47") (name "TRQ_AMP_L") (class "Default")
      (node (ref "U10") (pin "41") (pinfunction "A17_41") (pintype "bidirectional"))
    )
    (net (code "48") (name "TRQ_AMP_L1") (class "Default")
      (node (ref "C18") (pin "1") (pinfunction "1_1") (pintype "passive"))
      (node (ref "U10") (pin "40") (pinfunction "A16_40") (pintype "bidirectional"))
      (node (ref "U3") (pin "10") (pinfunction "VO_10") (pintype "output"))
      (node (ref "U3") (pin "11") (pinfunction "SENSE_11") (pintype "passive"))
    )
    (net (code "49") (name "TRQ_AMP_R") (class "Default")
      (node (ref "U10") (pin "21") (pinfunction "A7_21") (pintype "bidirectional"))
    )
    (net (code "50") (name "TRQ_AMP_R1") (class "Default")
      (node (ref "C10") (pin "1") (pinfunction "1_1") (pintype "passive"))
      (node (ref "U10") (pin "20") (pinfunction "A6_20") (pintype "bidirectional"))
      (node (ref "U4") (pin "10") (pinfunction "VO_10") (pintype "output"))
      (node (ref "U4") (pin "11") (pinfunction "SENSE_11") (pintype "passive"))
    )
    (net (code "51") (name "VCC1") (class "Default")
      (node (ref "R2") (pin "2") (pinfunction "2_2") (pintype "passive"))
      (node (ref "SHUNT") (pin "2") (pinfunction "2_2") (pintype "passive"))
      (node (ref "XT30UPB-F") (pin "+") (pinfunction "+_+") (pintype "output"))
      (node (ref "XT30UPB-F1") (pin "+") (pinfunction "+_+") (pintype "output"))
      (node (ref "XT30UPB-F2") (pin "+") (pinfunction "+_+") (pintype "output"))
      (node (ref "XT30UPB-F3") (pin "+") (pinfunction "+_+") (pintype "output"))
      (node (ref "XT30UPB-F4") (pin "+") (pinfunction "+_+") (pintype "output"))
    )
    (net (code "52") (name "VIN") (class "Default")
      (node (ref "C15") (pin "1") (pinfunction "1_1") (pintype "passive"))
      (node (ref "C3") (pin "2") (pinfunction "2_2") (pintype "passive"))
      (node (ref "C5") (pin "1") (pinfunction "1_1") (pintype "passive"))
      (node (ref "INA219") (pin "5") (pinfunction "VS_5") (pintype "power_in"))
      (node (ref "U$11") (pin "3") (pinfunction "+VOUT/GND_3") (pintype "power_in"))
      (node (ref "U$6") (pin "1") (pinfunction "P$1_1") (pintype "bidirectional"))
    )
    (net (code "53") (name "VIN_PF") (class "Default")
      (node (ref "C23") (pin "2") (pinfunction "2_2") (pintype "passive"))
      (node (ref "FAN") (pin "1") (pinfunction "1_1") (pintype "passive"))
      (node (ref "U$6") (pin "2") (pinfunction "P$2_2") (pintype "bidirectional"))
      (node (ref "U10") (pin "VIN") (pinfunction "VIN_VIN") (pintype "input"))
      (node (ref "USB") (pin "A15") (pinfunction "VIN_A15") (pintype "bidirectional"))
    )
    (net (code "54") (name "unconnected-(CAN_L0-SHIELD1-PadS1)") (class "Default")
      (node (ref "CAN_L0") (pin "S1") (pinfunction "SHIELD1_S1") (pintype "passive"))
    )
    (net (code "55") (name "unconnected-(CAN_L0-SHIELD2-PadS2)") (class "Default")
      (node (ref "CAN_L0") (pin "S2") (pinfunction "SHIELD2_S2") (pintype "passive"))
    )
    (net (code "56") (name "unconnected-(CAN_L1-SHIELD1-PadS1)") (class "Default")
      (node (ref "CAN_L1") (pin "S1") (pinfunction "SHIELD1_S1") (pintype "passive"))
    )
    (net (code "57") (name "unconnected-(CAN_L1-SHIELD2-PadS2)") (class "Default")
      (node (ref "CAN_L1") (pin "S2") (pinfunction "SHIELD2_S2") (pintype "passive"))
    )
    (net (code "58") (name "unconnected-(CAN_R0-SHIELD1-PadS1)") (class "Default")
      (node (ref "CAN_R0") (pin "S1") (pinfunction "SHIELD1_S1") (pintype "passive"))
    )
    (net (code "59") (name "unconnected-(CAN_R0-SHIELD2-PadS2)") (class "Default")
      (node (ref "CAN_R0") (pin "S2") (pinfunction "SHIELD2_S2") (pintype "passive"))
    )
    (net (code "60") (name "unconnected-(CAN_R1-SHIELD1-PadS1)") (class "Default")
      (node (ref "CAN_R1") (pin "S1") (pinfunction "SHIELD1_S1") (pintype "passive"))
    )
    (net (code "61") (name "unconnected-(CAN_R1-SHIELD2-PadS2)") (class "Default")
      (node (ref "CAN_R1") (pin "S2") (pinfunction "SHIELD2_S2") (pintype "passive"))
    )
    (net (code "62") (name "unconnected-(U3-VREF2.5-Pad14)") (class "Default")
      (node (ref "U3") (pin "14") (pinfunction "VREF2.5_14") (pintype "power_in"))
    )
    (net (code "63") (name "unconnected-(U3-VREF5-Pad15)") (class "Default")
      (node (ref "U3") (pin "15") (pinfunction "VREF5_15") (pintype "power_in"))
    )
    (net (code "64") (name "unconnected-(U3-VREF10-Pad16)") (class "Default")
      (node (ref "U3") (pin "16") (pinfunction "VREF10_16") (pintype "power_in"))
    )
    (net (code "65") (name "unconnected-(U4-VREF2.5-Pad14)") (class "Default")
      (node (ref "U4") (pin "14") (pinfunction "VREF2.5_14") (pintype "power_in"))
    )
    (net (code "66") (name "unconnected-(U4-VREF5-Pad15)") (class "Default")
      (node (ref "U4") (pin "15") (pinfunction "VREF5_15") (pintype "power_in"))
    )
    (net (code "67") (name "unconnected-(U4-VREF10-Pad16)") (class "Default")
      (node (ref "U4") (pin "16") (pinfunction "VREF10_16") (pintype "power_in"))
    )
    (net (code "68") (name "unconnected-(U5-VREF-Pad5)") (class "Default")
      (node (ref "U5") (pin "5") (pinfunction "VREF_5") (pintype "output"))
    )
    (net (code "69") (name "unconnected-(U10-BCLK2-Pad4)") (class "Default")
      (node (ref "U10") (pin "4") (pinfunction "BCLK2_4") (pintype "bidirectional"))
    )
    (net (code "70") (name "unconnected-(U10-CRX3-Pad30)") (class "Default")
      (node (ref "U10") (pin "30") (pinfunction "CRX3_30") (pintype "bidirectional"))
    )
    (net (code "71") (name "unconnected-(U10-CS1-Pad10)") (class "Default")
      (node (ref "U10") (pin "10") (pinfunction "CS1_10") (pintype "bidirectional"))
    )
    (net (code "72") (name "unconnected-(U10-CS2-Pad36)") (class "Default")
      (node (ref "U10") (pin "36") (pinfunction "CS2_36") (pintype "bidirectional"))
    )
    (net (code "73") (name "unconnected-(U10-CS3-Pad37)") (class "Default")
      (node (ref "U10") (pin "37") (pinfunction "CS3_37") (pintype "bidirectional"))
    )
    (net (code "74") (name "unconnected-(U10-CTX3-Pad31)") (class "Default")
      (node (ref "U10") (pin "31") (pinfunction "CTX3_31") (pintype "bidirectional"))
    )
    (net (code "75") (name "unconnected-(U10-LRCLK2-Pad3)") (class "Default")
      (node (ref "U10") (pin "3") (pinfunction "LRCLK2_3") (pintype "bidirectional"))
    )
    (net (code "76") (name "unconnected-(U10-MCLK2-Pad33)") (class "Default")
      (node (ref "U10") (pin "33") (pinfunction "MCLK2_33") (pintype "bidirectional"))
    )
    (net (code "77") (name "unconnected-(U10-MISO-Pad12)") (class "Default")
      (node (ref "U10") (pin "12") (pinfunction "MISO_12") (pintype "bidirectional"))
    )
    (net (code "78") (name "unconnected-(U10-MOSI-Pad11)") (class "Default")
      (node (ref "U10") (pin "11") (pinfunction "MOSI_11") (pintype "bidirectional"))
    )
    (net (code "79") (name "unconnected-(U10-OUT1B-Pad32)") (class "Default")
      (node (ref "U10") (pin "32") (pinfunction "OUT1B_32") (pintype "output"))
    )
    (net (code "80") (name "unconnected-(U10-OUT1D-Pad6)") (class "Default")
      (node (ref "U10") (pin "6") (pinfunction "OUT1D_6") (pintype "output"))
    )
    (net (code "81") (name "unconnected-(U10-OUT2-Pad2)") (class "Default")
      (node (ref "U10") (pin "2") (pinfunction "OUT2_2") (pintype "output"))
    )
    (net (code "82") (name "unconnected-(U10-PadPROGRAM)") (class "Default")
      (node (ref "U10") (pin "PROGRAM") (pinfunction "PROGRAM_PROGRAM") (pintype "bidirectional"))
    )
    (net (code "83") (name "unconnected-(U10-RX2-Pad7)") (class "Default")
      (node (ref "U10") (pin "7") (pinfunction "RX2_7") (pintype "bidirectional"))
    )
    (net (code "84") (name "unconnected-(U10-RX7-Pad28)") (class "Default")
      (node (ref "U10") (pin "28") (pinfunction "RX7_28") (pintype "bidirectional"))
    )
    (net (code "85") (name "unconnected-(U10-SCK-Pad13)") (class "Default")
      (node (ref "U10") (pin "13") (pinfunction "SCK_13") (pintype "bidirectional"))
    )
    (net (code "86") (name "unconnected-(U10-TX2-Pad8)") (class "Default")
      (node (ref "U10") (pin "8") (pinfunction "TX2_8") (pintype "bidirectional"))
    )
    (net (code "87") (name "unconnected-(U10-TX7-Pad29)") (class "Default")
      (node (ref "U10") (pin "29") (pinfunction "TX7_29") (pintype "bidirectional"))
    )
    (net (code "88") (name "unconnected-(USB-3.3V-PadA2)") (class "Default")
      (node (ref "USB") (pin "A2") (pinfunction "3.3V_A2") (pintype "bidirectional"))
    )
    (net (code "89") (name "unconnected-(USB-5V-PadA12)") (class "Default")
      (node (ref "USB") (pin "A12") (pinfunction "5V_A12") (pintype "bidirectional"))
    )
    (net (code "90") (name "unconnected-(USB-A0-PadA4)") (class "Default")
      (node (ref "USB") (pin "A4") (pinfunction "A0_A4") (pintype "bidirectional"))
    )
    (net (code "91") (name "unconnected-(USB-A1-PadA5)") (class "Default")
      (node (ref "USB") (pin "A5") (pinfunction "A1_A5") (pintype "bidirectional"))
    )
    (net (code "92") (name "unconnected-(USB-A2-PadA6)") (class "Default")
      (node (ref "USB") (pin "A6") (pinfunction "A2_A6") (pintype "bidirectional"))
    )
    (net (code "93") (name "unconnected-(USB-A3-PadA7)") (class "Default")
      (node (ref "USB") (pin "A7") (pinfunction "A3_A7") (pintype "bidirectional"))
    )
    (net (code "94") (name "unconnected-(USB-A6-PadA10)") (class "Default")
      (node (ref "USB") (pin "A10") (pinfunction "A6_A10") (pintype "bidirectional"))
    )
    (net (code "95") (name "unconnected-(USB-A7-PadA11)") (class "Default")
      (node (ref "USB") (pin "A11") (pinfunction "A7_A11") (pintype "bidirectional"))
    )
    (net (code "96") (name "unconnected-(USB-D2-PadB5)") (class "Default")
      (node (ref "USB") (pin "B5") (pinfunction "D2_B5") (pintype "bidirectional"))
    )
    (net (code "97") (name "unconnected-(USB-D3-PadB6)") (class "Default")
      (node (ref "USB") (pin "B6") (pinfunction "D3_B6") (pintype "bidirectional"))
    )
    (net (code "98") (name "unconnected-(USB-D4-PadB7)") (class "Default")
      (node (ref "USB") (pin "B7") (pinfunction "D4_B7") (pintype "bidirectional"))
    )
    (net (code "99") (name "unconnected-(USB-D5-PadB8)") (class "Default")
      (node (ref "USB") (pin "B8") (pinfunction "D5_B8") (pintype "bidirectional"))
    )
    (net (code "100") (name "unconnected-(USB-D6-PadB9)") (class "Default")
      (node (ref "USB") (pin "B9") (pinfunction "D6_B9") (pintype "bidirectional"))
    )
    (net (code "101") (name "unconnected-(USB-D7-PadB10)") (class "Default")
      (node (ref "USB") (pin "B10") (pinfunction "D7_B10") (pintype "bidirectional"))
    )
    (net (code "102") (name "unconnected-(USB-D8-PadB11)") (class "Default")
      (node (ref "USB") (pin "B11") (pinfunction "D8_B11") (pintype "bidirectional"))
    )
    (net (code "103") (name "unconnected-(USB-D9-PadB12)") (class "Default")
      (node (ref "USB") (pin "B12") (pinfunction "D9_B12") (pintype "bidirectional"))
    )
    (net (code "104") (name "unconnected-(USB-D10-PadB13)") (class "Default")
      (node (ref "USB") (pin "B13") (pinfunction "D10_B13") (pintype "bidirectional"))
    )
    (net (code "105") (name "unconnected-(USB-D11-PadB14)") (class "Default")
      (node (ref "USB") (pin "B14") (pinfunction "D11_B14") (pintype "bidirectional"))
    )
    (net (code "106") (name "unconnected-(USB-D12-PadB15)") (class "Default")
      (node (ref "USB") (pin "B15") (pinfunction "D12_B15") (pintype "bidirectional"))
    )
    (net (code "107") (name "unconnected-(USB-D13-PadA1)") (class "Default")
      (node (ref "USB") (pin "A1") (pinfunction "D13_A1") (pintype "bidirectional"))
    )
    (net (code "108") (name "unconnected-(USB-PadMH1)") (class "Default")
      (node (ref "USB") (pin "MH1") (pinfunction "MH1_MH1") (pintype "bidirectional"))
    )
    (net (code "109") (name "unconnected-(USB-PadMH2)") (class "Default")
      (node (ref "USB") (pin "MH2") (pinfunction "MH2_MH2") (pintype "bidirectional"))
    )
    (net (code "110") (name "unconnected-(USB-PadMH3)") (class "Default")
      (node (ref "USB") (pin "MH3") (pinfunction "MH3_MH3") (pintype "bidirectional"))
    )
    (net (code "111") (name "unconnected-(USB-PadMH4)") (class "Default")
      (node (ref "USB") (pin "MH4") (pinfunction "MH4_MH4") (pintype "bidirectional"))
    )
    (net (code "112") (name "unconnected-(USB-REF-PadA3)") (class "Default")
      (node (ref "USB") (pin "A3") (pinfunction "REF_A3") (pintype "bidirectional"))
    )
    (net (code "113") (name "unconnected-(USB-RST_2-PadB3)") (class "Default")
      (node (ref "USB") (pin "B3") (pinfunction "RST_2_B3") (pintype "bidirectional"))
    )
  )
)
